# NTC.net
KiCad netlist of a schematic drawn in Altium Designer
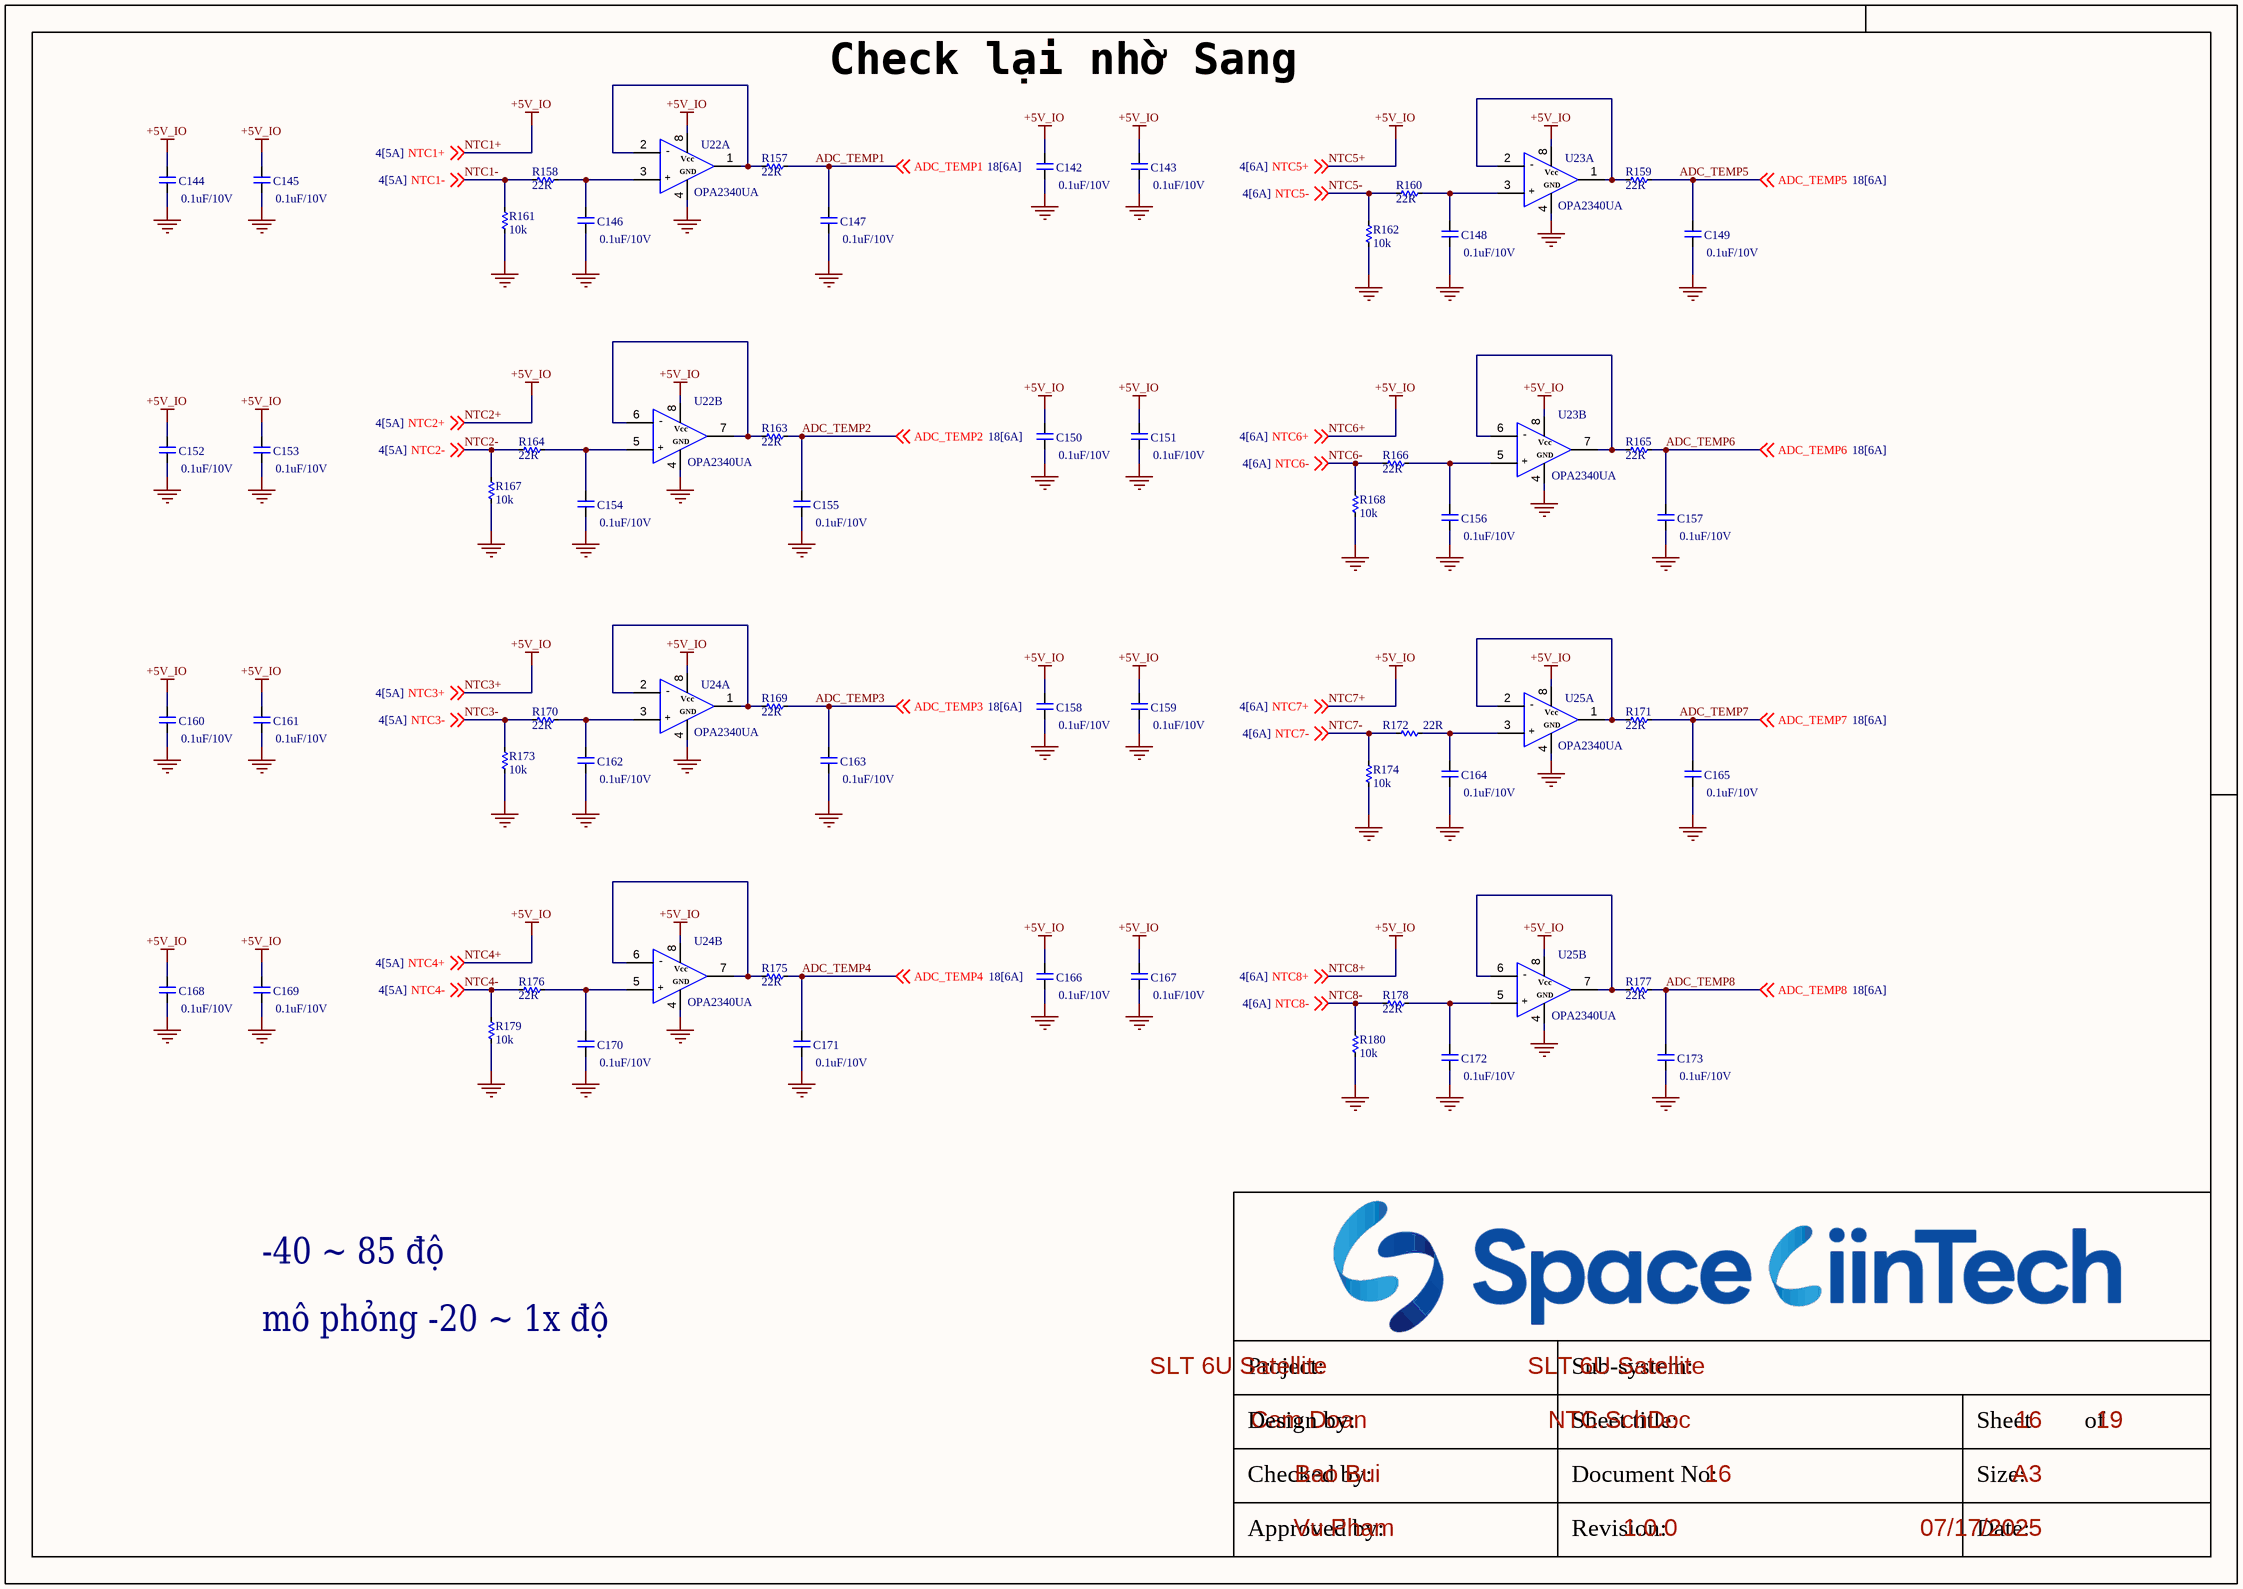
[diagram p0: NTC.SchDoc]

(export (version "E")
  (design (tool "Eeschema 10.0.6"))
  (components
    (comp (ref "C142")
      (value "0.1uF/10V")
      (footprint "CAP_C_1005X60")
      (description "CAP CHIP")
      (libsource (lib "LABLIB") (part "_CAP_C_2"))
    )
    (comp (ref "C143")
      (value "0.1uF/10V")
      (footprint "CAP_C_1005X60")
      (description "CAP CHIP")
      (libsource (lib "LABLIB") (part "_CAP_C_2"))
    )
    (comp (ref "C144")
      (value "0.1uF/10V")
      (footprint "CAP_C_1005X60")
      (description "CAP CHIP")
      (libsource (lib "LABLIB") (part "_CAP_C_2"))
    )
    (comp (ref "C145")
      (value "0.1uF/10V")
      (footprint "CAP_C_1005X60")
      (description "CAP CHIP")
      (libsource (lib "LABLIB") (part "_CAP_C_2"))
    )
    (comp (ref "C146")
      (value "0.1uF/10V")
      (footprint "CAP_C_1005X60")
      (description "CAP CHIP")
      (libsource (lib "LABLIB") (part "_CAP_C_2"))
    )
    (comp (ref "C147")
      (value "0.1uF/10V")
      (footprint "CAP_C_1005X60")
      (description "CAP CHIP")
      (libsource (lib "LABLIB") (part "_CAP_C_2"))
    )
    (comp (ref "C148")
      (value "0.1uF/10V")
      (footprint "CAP_C_1005X60")
      (description "CAP CHIP")
      (libsource (lib "LABLIB") (part "_CAP_C_2"))
    )
    (comp (ref "C149")
      (value "0.1uF/10V")
      (footprint "CAP_C_1005X60")
      (description "CAP CHIP")
      (libsource (lib "LABLIB") (part "_CAP_C_2"))
    )
    (comp (ref "C150")
      (value "0.1uF/10V")
      (footprint "CAP_C_1005X60")
      (description "CAP CHIP")
      (libsource (lib "LABLIB") (part "_CAP_C_2"))
    )
    (comp (ref "C151")
      (value "0.1uF/10V")
      (footprint "CAP_C_1005X60")
      (description "CAP CHIP")
      (libsource (lib "LABLIB") (part "_CAP_C_2"))
    )
    (comp (ref "C152")
      (value "0.1uF/10V")
      (footprint "CAP_C_1005X60")
      (description "CAP CHIP")
      (libsource (lib "LABLIB") (part "_CAP_C_2"))
    )
    (comp (ref "C153")
      (value "0.1uF/10V")
      (footprint "CAP_C_1005X60")
      (description "CAP CHIP")
      (libsource (lib "LABLIB") (part "_CAP_C_2"))
    )
    (comp (ref "C154")
      (value "0.1uF/10V")
      (footprint "CAP_C_1005X60")
      (description "CAP CHIP")
      (libsource (lib "LABLIB") (part "_CAP_C_2"))
    )
    (comp (ref "C155")
      (value "0.1uF/10V")
      (footprint "CAP_C_1005X60")
      (description "CAP CHIP")
      (libsource (lib "LABLIB") (part "_CAP_C_2"))
    )
    (comp (ref "C156")
      (value "0.1uF/10V")
      (footprint "CAP_C_1005X60")
      (description "CAP CHIP")
      (libsource (lib "LABLIB") (part "_CAP_C_2"))
    )
    (comp (ref "C157")
      (value "0.1uF/10V")
      (footprint "CAP_C_1005X60")
      (description "CAP CHIP")
      (libsource (lib "LABLIB") (part "_CAP_C_2"))
    )
    (comp (ref "C158")
      (value "0.1uF/10V")
      (footprint "CAP_C_1005X60")
      (description "CAP CHIP")
      (libsource (lib "LABLIB") (part "_CAP_C_2"))
    )
    (comp (ref "C159")
      (value "0.1uF/10V")
      (footprint "CAP_C_1005X60")
      (description "CAP CHIP")
      (libsource (lib "LABLIB") (part "_CAP_C_2"))
    )
    (comp (ref "C160")
      (value "0.1uF/10V")
      (footprint "CAP_C_1005X60")
      (description "CAP CHIP")
      (libsource (lib "LABLIB") (part "_CAP_C_2"))
    )
    (comp (ref "C161")
      (value "0.1uF/10V")
      (footprint "CAP_C_1005X60")
      (description "CAP CHIP")
      (libsource (lib "LABLIB") (part "_CAP_C_2"))
    )
    (comp (ref "C162")
      (value "0.1uF/10V")
      (footprint "CAP_C_1005X60")
      (description "CAP CHIP")
      (libsource (lib "LABLIB") (part "_CAP_C_2"))
    )
    (comp (ref "C163")
      (value "0.1uF/10V")
      (footprint "CAP_C_1005X60")
      (description "CAP CHIP")
      (libsource (lib "LABLIB") (part "_CAP_C_2"))
    )
    (comp (ref "C164")
      (value "0.1uF/10V")
      (footprint "CAP_C_1005X60")
      (description "CAP CHIP")
      (libsource (lib "LABLIB") (part "_CAP_C_2"))
    )
    (comp (ref "C165")
      (value "0.1uF/10V")
      (footprint "CAP_C_1005X60")
      (description "CAP CHIP")
      (libsource (lib "LABLIB") (part "_CAP_C_2"))
    )
    (comp (ref "C166")
      (value "0.1uF/10V")
      (footprint "CAP_C_1005X60")
      (description "CAP CHIP")
      (libsource (lib "LABLIB") (part "_CAP_C_2"))
    )
    (comp (ref "C167")
      (value "0.1uF/10V")
      (footprint "CAP_C_1005X60")
      (description "CAP CHIP")
      (libsource (lib "LABLIB") (part "_CAP_C_2"))
    )
    (comp (ref "C168")
      (value "0.1uF/10V")
      (footprint "CAP_C_1005X60")
      (description "CAP CHIP")
      (libsource (lib "LABLIB") (part "_CAP_C_2"))
    )
    (comp (ref "C169")
      (value "0.1uF/10V")
      (footprint "CAP_C_1005X60")
      (description "CAP CHIP")
      (libsource (lib "LABLIB") (part "_CAP_C_2"))
    )
    (comp (ref "C170")
      (value "0.1uF/10V")
      (footprint "CAP_C_1005X60")
      (description "CAP CHIP")
      (libsource (lib "LABLIB") (part "_CAP_C_2"))
    )
    (comp (ref "C171")
      (value "0.1uF/10V")
      (footprint "CAP_C_1005X60")
      (description "CAP CHIP")
      (libsource (lib "LABLIB") (part "_CAP_C_2"))
    )
    (comp (ref "C172")
      (value "0.1uF/10V")
      (footprint "CAP_C_1005X60")
      (description "CAP CHIP")
      (libsource (lib "LABLIB") (part "_CAP_C_2"))
    )
    (comp (ref "C173")
      (value "0.1uF/10V")
      (footprint "CAP_C_1005X60")
      (description "CAP CHIP")
      (libsource (lib "LABLIB") (part "_CAP_C_2"))
    )
    (comp (ref "R157")
      (value "22R")
      (footprint "RES_C_1005X40")
      (description "RES")
      (libsource (lib "LABLIB") (part "_RES_B_2"))
    )
    (comp (ref "R158")
      (value "22R")
      (footprint "RES_C_1005X40")
      (description "RES")
      (libsource (lib "LABLIB") (part "_RES_B_2"))
    )
    (comp (ref "R159")
      (value "22R")
      (footprint "RES_C_1005X40")
      (description "RES")
      (libsource (lib "LABLIB") (part "_RES_B_2"))
    )
    (comp (ref "R160")
      (value "22R")
      (footprint "RES_C_1005X40")
      (description "RES")
      (libsource (lib "LABLIB") (part "_RES_B_2"))
    )
    (comp (ref "R161")
      (value "10k")
      (footprint "RES_C_1005X40")
      (description "RES")
      (libsource (lib "LABLIB") (part "_RES_B_2"))
    )
    (comp (ref "R162")
      (value "10k")
      (footprint "RES_C_1005X40")
      (description "RES")
      (libsource (lib "LABLIB") (part "_RES_B_2"))
    )
    (comp (ref "R163")
      (value "22R")
      (footprint "RES_C_1005X40")
      (description "RES")
      (libsource (lib "LABLIB") (part "_RES_B_2"))
    )
    (comp (ref "R164")
      (value "22R")
      (footprint "RES_C_1005X40")
      (description "RES")
      (libsource (lib "LABLIB") (part "_RES_B_2"))
    )
    (comp (ref "R165")
      (value "22R")
      (footprint "RES_C_1005X40")
      (description "RES")
      (libsource (lib "LABLIB") (part "_RES_B_2"))
    )
    (comp (ref "R166")
      (value "22R")
      (footprint "RES_C_1005X40")
      (description "RES")
      (libsource (lib "LABLIB") (part "_RES_B_2"))
    )
    (comp (ref "R167")
      (value "10k")
      (footprint "RES_C_1005X40")
      (description "RES")
      (libsource (lib "LABLIB") (part "_RES_B_2"))
    )
    (comp (ref "R168")
      (value "10k")
      (footprint "RES_C_1005X40")
      (description "RES")
      (libsource (lib "LABLIB") (part "_RES_B_2"))
    )
    (comp (ref "R169")
      (value "22R")
      (footprint "RES_C_1005X40")
      (description "RES")
      (libsource (lib "LABLIB") (part "_RES_B_2"))
    )
    (comp (ref "R170")
      (value "22R")
      (footprint "RES_C_1005X40")
      (description "RES")
      (libsource (lib "LABLIB") (part "_RES_B_2"))
    )
    (comp (ref "R171")
      (value "22R")
      (footprint "RES_C_1005X40")
      (description "RES")
      (libsource (lib "LABLIB") (part "_RES_B_2"))
    )
    (comp (ref "R172")
      (value "22R")
      (footprint "RES_C_1005X40")
      (description "RES")
      (libsource (lib "LABLIB") (part "_RES_B_2"))
    )
    (comp (ref "R173")
      (value "10k")
      (footprint "RES_C_1005X40")
      (description "RES")
      (libsource (lib "LABLIB") (part "_RES_B_2"))
    )
    (comp (ref "R174")
      (value "10k")
      (footprint "RES_C_1005X40")
      (description "RES")
      (libsource (lib "LABLIB") (part "_RES_B_2"))
    )
    (comp (ref "R175")
      (value "22R")
      (footprint "RES_C_1005X40")
      (description "RES")
      (libsource (lib "LABLIB") (part "_RES_B_2"))
    )
    (comp (ref "R176")
      (value "22R")
      (footprint "RES_C_1005X40")
      (description "RES")
      (libsource (lib "LABLIB") (part "_RES_B_2"))
    )
    (comp (ref "R177")
      (value "22R")
      (footprint "RES_C_1005X40")
      (description "RES")
      (libsource (lib "LABLIB") (part "_RES_B_2"))
    )
    (comp (ref "R178")
      (value "22R")
      (footprint "RES_C_1005X40")
      (description "RES")
      (libsource (lib "LABLIB") (part "_RES_B_2"))
    )
    (comp (ref "R179")
      (value "10k")
      (footprint "RES_C_1005X40")
      (description "RES")
      (libsource (lib "LABLIB") (part "_RES_B_2"))
    )
    (comp (ref "R180")
      (value "10k")
      (footprint "RES_C_1005X40")
      (description "RES")
      (libsource (lib "LABLIB") (part "_RES_B_2"))
    )
    (comp (ref "U22")
      (value "OPA2340UA")
      (footprint "SOIC127P602X173-8N")
      (libsource (lib "EXP_HW_V3") (part "OPA2340UA"))
    )
    (comp (ref "U23")
      (value "OPA2340UA")
      (footprint "SOIC127P602X173-8N")
      (libsource (lib "EXP_HW_V3") (part "OPA2340UA"))
    )
    (comp (ref "U24")
      (value "OPA2340UA")
      (footprint "SOIC127P602X173-8N")
      (libsource (lib "EXP_HW_V3") (part "OPA2340UA"))
    )
    (comp (ref "U25")
      (value "OPA2340UA")
      (footprint "SOIC127P602X173-8N")
      (libsource (lib "EXP_HW_V3") (part "OPA2340UA"))
    )
  )
  (nets
    (net (code "1") (name "+5V_IO") (class "Default")
      (node (ref "C142") (pin "2") (pinfunction "2_2") (pintype "passive"))
      (node (ref "C143") (pin "2") (pinfunction "2_2") (pintype "passive"))
      (node (ref "C144") (pin "2") (pinfunction "2_2") (pintype "passive"))
      (node (ref "C145") (pin "2") (pinfunction "2_2") (pintype "passive"))
      (node (ref "C150") (pin "2") (pinfunction "2_2") (pintype "passive"))
      (node (ref "C151") (pin "2") (pinfunction "2_2") (pintype "passive"))
      (node (ref "C152") (pin "2") (pinfunction "2_2") (pintype "passive"))
      (node (ref "C153") (pin "2") (pinfunction "2_2") (pintype "passive"))
      (node (ref "C158") (pin "2") (pinfunction "2_2") (pintype "passive"))
      (node (ref "C159") (pin "2") (pinfunction "2_2") (pintype "passive"))
      (node (ref "C160") (pin "2") (pinfunction "2_2") (pintype "passive"))
      (node (ref "C161") (pin "2") (pinfunction "2_2") (pintype "passive"))
      (node (ref "C166") (pin "2") (pinfunction "2_2") (pintype "passive"))
      (node (ref "C167") (pin "2") (pinfunction "2_2") (pintype "passive"))
      (node (ref "C168") (pin "2") (pinfunction "2_2") (pintype "passive"))
      (node (ref "C169") (pin "2") (pinfunction "2_2") (pintype "passive"))
      (node (ref "U22") (pin "8") (pinfunction "8_8") (pintype "passive"))
      (node (ref "U23") (pin "8") (pinfunction "8_8") (pintype "passive"))
      (node (ref "U24") (pin "8") (pinfunction "8_8") (pintype "passive"))
      (node (ref "U25") (pin "8") (pinfunction "8_8") (pintype "passive"))
    )
    (net (code "2") (name "ADC_TEMP1") (class "Default")
      (node (ref "C147") (pin "2") (pinfunction "2_2") (pintype "passive"))
      (node (ref "R157") (pin "2") (pinfunction "2_2") (pintype "passive"))
    )
    (net (code "3") (name "ADC_TEMP2") (class "Default")
      (node (ref "C155") (pin "2") (pinfunction "2_2") (pintype "passive"))
      (node (ref "R163") (pin "2") (pinfunction "2_2") (pintype "passive"))
    )
    (net (code "4") (name "ADC_TEMP3") (class "Default")
      (node (ref "C163") (pin "2") (pinfunction "2_2") (pintype "passive"))
      (node (ref "R169") (pin "2") (pinfunction "2_2") (pintype "passive"))
    )
    (net (code "5") (name "ADC_TEMP4") (class "Default")
      (node (ref "C171") (pin "2") (pinfunction "2_2") (pintype "passive"))
      (node (ref "R175") (pin "2") (pinfunction "2_2") (pintype "passive"))
    )
    (net (code "6") (name "ADC_TEMP5") (class "Default")
      (node (ref "C149") (pin "2") (pinfunction "2_2") (pintype "passive"))
      (node (ref "R159") (pin "2") (pinfunction "2_2") (pintype "passive"))
    )
    (net (code "7") (name "ADC_TEMP6") (class "Default")
      (node (ref "C157") (pin "2") (pinfunction "2_2") (pintype "passive"))
      (node (ref "R165") (pin "2") (pinfunction "2_2") (pintype "passive"))
    )
    (net (code "8") (name "ADC_TEMP7") (class "Default")
      (node (ref "C165") (pin "2") (pinfunction "2_2") (pintype "passive"))
      (node (ref "R171") (pin "2") (pinfunction "2_2") (pintype "passive"))
    )
    (net (code "9") (name "ADC_TEMP8") (class "Default")
      (node (ref "C173") (pin "2") (pinfunction "2_2") (pintype "passive"))
      (node (ref "R177") (pin "2") (pinfunction "2_2") (pintype "passive"))
    )
    (net (code "10") (name "GND") (class "Default")
      (node (ref "C142") (pin "1") (pinfunction "1_1") (pintype "passive"))
      (node (ref "C143") (pin "1") (pinfunction "1_1") (pintype "passive"))
      (node (ref "C144") (pin "1") (pinfunction "1_1") (pintype "passive"))
      (node (ref "C145") (pin "1") (pinfunction "1_1") (pintype "passive"))
      (node (ref "C146") (pin "1") (pinfunction "1_1") (pintype "passive"))
      (node (ref "C147") (pin "1") (pinfunction "1_1") (pintype "passive"))
      (node (ref "C148") (pin "1") (pinfunction "1_1") (pintype "passive"))
      (node (ref "C149") (pin "1") (pinfunction "1_1") (pintype "passive"))
      (node (ref "C150") (pin "1") (pinfunction "1_1") (pintype "passive"))
      (node (ref "C151") (pin "1") (pinfunction "1_1") (pintype "passive"))
      (node (ref "C152") (pin "1") (pinfunction "1_1") (pintype "passive"))
      (node (ref "C153") (pin "1") (pinfunction "1_1") (pintype "passive"))
      (node (ref "C154") (pin "1") (pinfunction "1_1") (pintype "passive"))
      (node (ref "C155") (pin "1") (pinfunction "1_1") (pintype "passive"))
      (node (ref "C156") (pin "1") (pinfunction "1_1") (pintype "passive"))
      (node (ref "C157") (pin "1") (pinfunction "1_1") (pintype "passive"))
      (node (ref "C158") (pin "1") (pinfunction "1_1") (pintype "passive"))
      (node (ref "C159") (pin "1") (pinfunction "1_1") (pintype "passive"))
      (node (ref "C160") (pin "1") (pinfunction "1_1") (pintype "passive"))
      (node (ref "C161") (pin "1") (pinfunction "1_1") (pintype "passive"))
      (node (ref "C162") (pin "1") (pinfunction "1_1") (pintype "passive"))
      (node (ref "C163") (pin "1") (pinfunction "1_1") (pintype "passive"))
      (node (ref "C164") (pin "1") (pinfunction "1_1") (pintype "passive"))
      (node (ref "C165") (pin "1") (pinfunction "1_1") (pintype "passive"))
      (node (ref "C166") (pin "1") (pinfunction "1_1") (pintype "passive"))
      (node (ref "C167") (pin "1") (pinfunction "1_1") (pintype "passive"))
      (node (ref "C168") (pin "1") (pinfunction "1_1") (pintype "passive"))
      (node (ref "C169") (pin "1") (pinfunction "1_1") (pintype "passive"))
      (node (ref "C170") (pin "1") (pinfunction "1_1") (pintype "passive"))
      (node (ref "C171") (pin "1") (pinfunction "1_1") (pintype "passive"))
      (node (ref "C172") (pin "1") (pinfunction "1_1") (pintype "passive"))
      (node (ref "C173") (pin "1") (pinfunction "1_1") (pintype "passive"))
      (node (ref "R161") (pin "1") (pinfunction "1_1") (pintype "passive"))
      (node (ref "R162") (pin "1") (pinfunction "1_1") (pintype "passive"))
      (node (ref "R167") (pin "1") (pinfunction "1_1") (pintype "passive"))
      (node (ref "R168") (pin "1") (pinfunction "1_1") (pintype "passive"))
      (node (ref "R173") (pin "1") (pinfunction "1_1") (pintype "passive"))
      (node (ref "R174") (pin "1") (pinfunction "1_1") (pintype "passive"))
      (node (ref "R179") (pin "1") (pinfunction "1_1") (pintype "passive"))
      (node (ref "R180") (pin "1") (pinfunction "1_1") (pintype "passive"))
      (node (ref "U22") (pin "4") (pinfunction "4_4") (pintype "passive"))
      (node (ref "U23") (pin "4") (pinfunction "4_4") (pintype "passive"))
      (node (ref "U24") (pin "4") (pinfunction "4_4") (pintype "passive"))
      (node (ref "U25") (pin "4") (pinfunction "4_4") (pintype "passive"))
    )
    (net (code "11") (name "NTC1-") (class "Default")
      (node (ref "R158") (pin "1") (pinfunction "1_1") (pintype "passive"))
      (node (ref "R161") (pin "2") (pinfunction "2_2") (pintype "passive"))
    )
    (net (code "12") (name "NTC2-") (class "Default")
      (node (ref "R164") (pin "1") (pinfunction "1_1") (pintype "passive"))
      (node (ref "R167") (pin "2") (pinfunction "2_2") (pintype "passive"))
    )
    (net (code "13") (name "NTC3-") (class "Default")
      (node (ref "R170") (pin "1") (pinfunction "1_1") (pintype "passive"))
      (node (ref "R173") (pin "2") (pinfunction "2_2") (pintype "passive"))
    )
    (net (code "14") (name "NTC4-") (class "Default")
      (node (ref "R176") (pin "1") (pinfunction "1_1") (pintype "passive"))
      (node (ref "R179") (pin "2") (pinfunction "2_2") (pintype "passive"))
    )
    (net (code "15") (name "NTC5-") (class "Default")
      (node (ref "R160") (pin "1") (pinfunction "1_1") (pintype "passive"))
      (node (ref "R162") (pin "2") (pinfunction "2_2") (pintype "passive"))
    )
    (net (code "16") (name "NTC6-") (class "Default")
      (node (ref "R166") (pin "1") (pinfunction "1_1") (pintype "passive"))
      (node (ref "R168") (pin "2") (pinfunction "2_2") (pintype "passive"))
    )
    (net (code "17") (name "NTC7-") (class "Default")
      (node (ref "R172") (pin "1") (pinfunction "1_1") (pintype "passive"))
      (node (ref "R174") (pin "2") (pinfunction "2_2") (pintype "passive"))
    )
    (net (code "18") (name "NTC8-") (class "Default")
      (node (ref "R178") (pin "1") (pinfunction "1_1") (pintype "passive"))
      (node (ref "R180") (pin "2") (pinfunction "2_2") (pintype "passive"))
    )
    (net (code "19") (name "Net-(C146-Pad2)") (class "Default")
      (node (ref "C146") (pin "2") (pinfunction "2_2") (pintype "passive"))
      (node (ref "R158") (pin "2") (pinfunction "2_2") (pintype "passive"))
      (node (ref "U22") (pin "3") (pinfunction "3_3") (pintype "passive"))
    )
    (net (code "20") (name "Net-(C148-Pad2)") (class "Default")
      (node (ref "C148") (pin "2") (pinfunction "2_2") (pintype "passive"))
      (node (ref "R160") (pin "2") (pinfunction "2_2") (pintype "passive"))
      (node (ref "U23") (pin "3") (pinfunction "3_3") (pintype "passive"))
    )
    (net (code "21") (name "Net-(C154-Pad2)") (class "Default")
      (node (ref "C154") (pin "2") (pinfunction "2_2") (pintype "passive"))
      (node (ref "R164") (pin "2") (pinfunction "2_2") (pintype "passive"))
      (node (ref "U22") (pin "5") (pinfunction "5_5") (pintype "passive"))
    )
    (net (code "22") (name "Net-(C156-Pad2)") (class "Default")
      (node (ref "C156") (pin "2") (pinfunction "2_2") (pintype "passive"))
      (node (ref "R166") (pin "2") (pinfunction "2_2") (pintype "passive"))
      (node (ref "U23") (pin "5") (pinfunction "5_5") (pintype "passive"))
    )
    (net (code "23") (name "Net-(C162-Pad2)") (class "Default")
      (node (ref "C162") (pin "2") (pinfunction "2_2") (pintype "passive"))
      (node (ref "R170") (pin "2") (pinfunction "2_2") (pintype "passive"))
      (node (ref "U24") (pin "3") (pinfunction "3_3") (pintype "passive"))
    )
    (net (code "24") (name "Net-(C164-Pad2)") (class "Default")
      (node (ref "C164") (pin "2") (pinfunction "2_2") (pintype "passive"))
      (node (ref "R172") (pin "2") (pinfunction "2_2") (pintype "passive"))
      (node (ref "U25") (pin "3") (pinfunction "3_3") (pintype "passive"))
    )
    (net (code "25") (name "Net-(C170-Pad2)") (class "Default")
      (node (ref "C170") (pin "2") (pinfunction "2_2") (pintype "passive"))
      (node (ref "R176") (pin "2") (pinfunction "2_2") (pintype "passive"))
      (node (ref "U24") (pin "5") (pinfunction "5_5") (pintype "passive"))
    )
    (net (code "26") (name "Net-(C172-Pad2)") (class "Default")
      (node (ref "C172") (pin "2") (pinfunction "2_2") (pintype "passive"))
      (node (ref "R178") (pin "2") (pinfunction "2_2") (pintype "passive"))
      (node (ref "U25") (pin "5") (pinfunction "5_5") (pintype "passive"))
    )
    (net (code "27") (name "Net-(R157-Pad1)") (class "Default")
      (node (ref "R157") (pin "1") (pinfunction "1_1") (pintype "passive"))
      (node (ref "U22") (pin "1") (pinfunction "1_1") (pintype "passive"))
      (node (ref "U22") (pin "2") (pinfunction "2_2") (pintype "passive"))
    )
    (net (code "28") (name "Net-(R159-Pad1)") (class "Default")
      (node (ref "R159") (pin "1") (pinfunction "1_1") (pintype "passive"))
      (node (ref "U23") (pin "1") (pinfunction "1_1") (pintype "passive"))
      (node (ref "U23") (pin "2") (pinfunction "2_2") (pintype "passive"))
    )
    (net (code "29") (name "Net-(R163-Pad1)") (class "Default")
      (node (ref "R163") (pin "1") (pinfunction "1_1") (pintype "passive"))
      (node (ref "U22") (pin "6") (pinfunction "6_6") (pintype "passive"))
      (node (ref "U22") (pin "7") (pinfunction "7_7") (pintype "passive"))
    )
    (net (code "30") (name "Net-(R165-Pad1)") (class "Default")
      (node (ref "R165") (pin "1") (pinfunction "1_1") (pintype "passive"))
      (node (ref "U23") (pin "6") (pinfunction "6_6") (pintype "passive"))
      (node (ref "U23") (pin "7") (pinfunction "7_7") (pintype "passive"))
    )
    (net (code "31") (name "Net-(R169-Pad1)") (class "Default")
      (node (ref "R169") (pin "1") (pinfunction "1_1") (pintype "passive"))
      (node (ref "U24") (pin "1") (pinfunction "1_1") (pintype "passive"))
      (node (ref "U24") (pin "2") (pinfunction "2_2") (pintype "passive"))
    )
    (net (code "32") (name "Net-(R171-Pad1)") (class "Default")
      (node (ref "R171") (pin "1") (pinfunction "1_1") (pintype "passive"))
      (node (ref "U25") (pin "1") (pinfunction "1_1") (pintype "passive"))
      (node (ref "U25") (pin "2") (pinfunction "2_2") (pintype "passive"))
    )
    (net (code "33") (name "Net-(R175-Pad1)") (class "Default")
      (node (ref "R175") (pin "1") (pinfunction "1_1") (pintype "passive"))
      (node (ref "U24") (pin "6") (pinfunction "6_6") (pintype "passive"))
      (node (ref "U24") (pin "7") (pinfunction "7_7") (pintype "passive"))
    )
    (net (code "34") (name "Net-(R177-Pad1)") (class "Default")
      (node (ref "R177") (pin "1") (pinfunction "1_1") (pintype "passive"))
      (node (ref "U25") (pin "6") (pinfunction "6_6") (pintype "passive"))
      (node (ref "U25") (pin "7") (pinfunction "7_7") (pintype "passive"))
    )
  )
)
